# SCH_First-pcp-Design_2024-06-27.net
KiCad netlist of a schematic drawn in EasyEDA
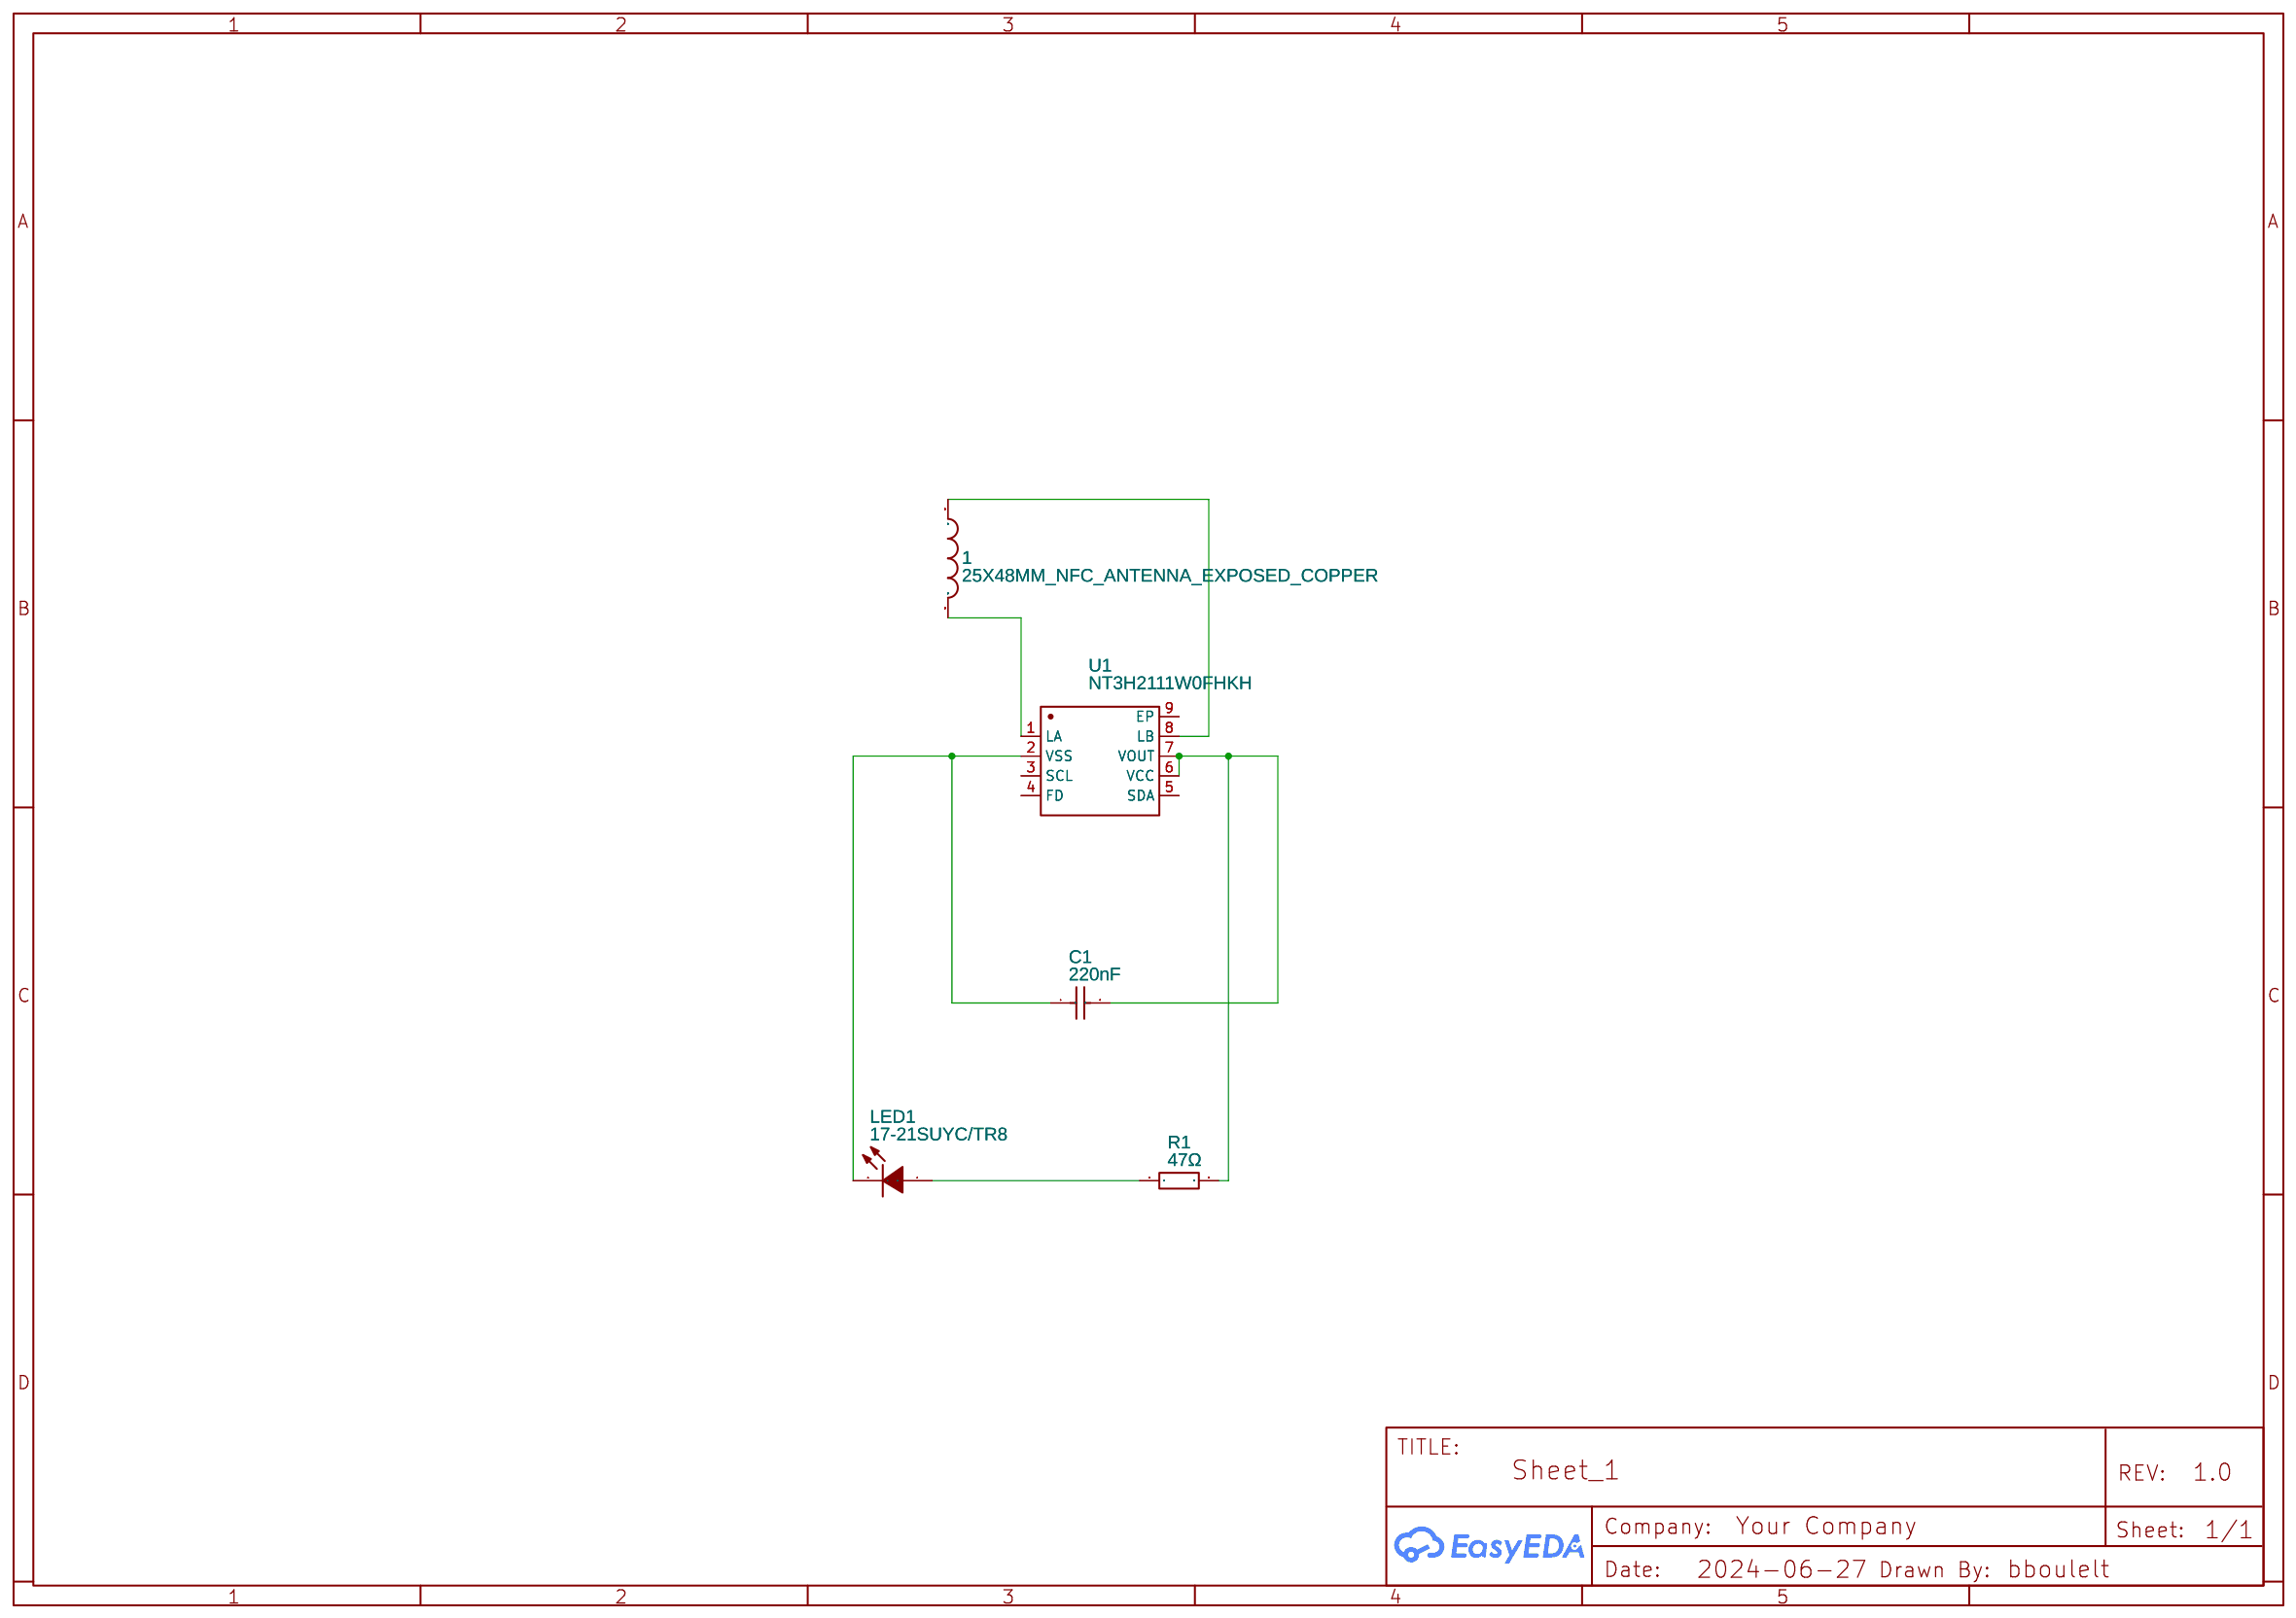
[diagram p0: schematic sheet]

(export (version "E")
  (design (tool "Eeschema 10.0.6"))
  (components
    (comp (ref "1")
      (value "25X48MM_NFC_ANTENNA_EXPOSED_COPPER")
      (libsource (lib "") (part "25X48MM_NFC_ANTENNA_EXPOSED_COPPER"))
    )
    (comp (ref "C1")
      (value "220nF")
      (fields
        (field (name "Manufacturer Part") "CL10B224KA8NNNC")
        (field (name "Manufacturer") "SAMSUNG(三星)")
      )
      (libsource (lib "") (part "CL10B224KA8NNNC"))
    )
    (comp (ref "LED1")
      (value "17-21SUYC/TR8")
      (fields (field (name "Manufacturer Part") "KT-0805黄灯") (field (name "Manufacturer") "KENTO"))
      (libsource (lib "") (part "17-21SUYC/TR8"))
    )
    (comp (ref "R1")
      (value "47Ω")
      (fields
        (field (name "Manufacturer Part") "0603WAF470JT5E")
        (field (name "Manufacturer") "UNI-ROYAL(厚声)")
      )
      (libsource (lib "") (part "0603WAF470JT5E"))
    )
    (comp (ref "U1")
      (value "NT3H2111W0FHKH")
      (fields (field (name "Manufacturer") "NXP(恩智浦)"))
      (libsource (lib "") (part "NT3H2111W0FHKH"))
    )
  )
  (nets
    (net (code "1") (name "Net-(LED1-+)") (class "Default")
      (node (ref "LED1") (pin "1") (pinfunction "+_1") (pintype "unspecified"))
      (node (ref "R1") (pin "1") (pinfunction "1_1") (pintype "input"))
    )
    (net (code "2") (name "Net-(LED1--)") (class "Default")
      (node (ref "C1") (pin "1") (pinfunction "1_1") (pintype "input"))
      (node (ref "LED1") (pin "2") (pinfunction "-_2") (pintype "unspecified"))
      (node (ref "U1") (pin "2") (pinfunction "VSS_2") (pintype "unspecified"))
    )
    (net (code "3") (name "Net-(U1-LA)") (class "Default")
      (node (ref "1") (pin "P$2") (pinfunction "P$2_P$2") (pintype "bidirectional"))
      (node (ref "U1") (pin "1") (pinfunction "LA_1") (pintype "unspecified"))
    )
    (net (code "4") (name "Net-(U1-LB)") (class "Default")
      (node (ref "1") (pin "P$1") (pinfunction "P$1_P$1") (pintype "bidirectional"))
      (node (ref "U1") (pin "8") (pinfunction "LB_8") (pintype "unspecified"))
    )
    (net (code "5") (name "Net-(U1-VCC)") (class "Default")
      (node (ref "C1") (pin "2") (pinfunction "2_2") (pintype "input"))
      (node (ref "R1") (pin "2") (pinfunction "2_2") (pintype "input"))
      (node (ref "U1") (pin "6") (pinfunction "VCC_6") (pintype "unspecified"))
      (node (ref "U1") (pin "7") (pinfunction "VOUT_7") (pintype "unspecified"))
    )
    (net (code "6") (name "unconnected-(U1-EP-Pad9)") (class "Default")
      (node (ref "U1") (pin "9") (pinfunction "EP_9") (pintype "unspecified"))
    )
    (net (code "7") (name "unconnected-(U1-FD-Pad4)") (class "Default")
      (node (ref "U1") (pin "4") (pinfunction "FD_4") (pintype "unspecified"))
    )
    (net (code "8") (name "unconnected-(U1-SCL-Pad3)") (class "Default")
      (node (ref "U1") (pin "3") (pinfunction "SCL_3") (pintype "unspecified"))
    )
    (net (code "9") (name "unconnected-(U1-SDA-Pad5)") (class "Default")
      (node (ref "U1") (pin "5") (pinfunction "SDA_5") (pintype "unspecified"))
    )
  )
)
